# Sensor_LED_2x6_PCB.net
KiCad netlist of a schematic drawn in EAGLE
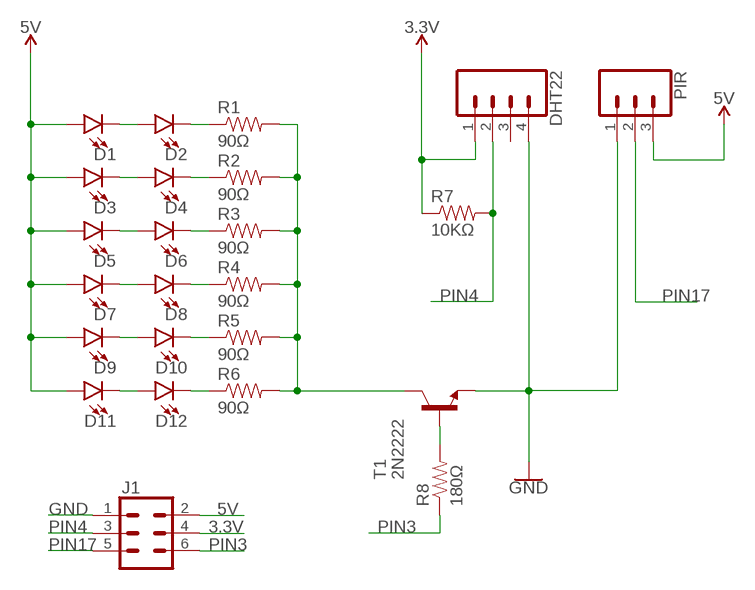
[diagram p0: schematic, sheet 1]

(export (version "E")
  (design (tool "Eeschema 10.0.6"))
  (components
    (comp (ref "D1")
      (value "LED5MM")
      (footprint "eagle-import:LED_5MM")
      (libsource (lib "eagle-import") (part "LED5MM"))
    )
    (comp (ref "D2")
      (value "LED5MM")
      (footprint "eagle-import:LED_5MM")
      (libsource (lib "eagle-import") (part "LED5MM"))
    )
    (comp (ref "D3")
      (value "LED5MM")
      (footprint "eagle-import:LED_5MM")
      (libsource (lib "eagle-import") (part "LED5MM"))
    )
    (comp (ref "D4")
      (value "LED5MM")
      (footprint "eagle-import:LED_5MM")
      (libsource (lib "eagle-import") (part "LED5MM"))
    )
    (comp (ref "D5")
      (value "LED5MM")
      (footprint "eagle-import:LED_5MM")
      (libsource (lib "eagle-import") (part "LED5MM"))
    )
    (comp (ref "D6")
      (value "LED5MM")
      (footprint "eagle-import:LED_5MM")
      (libsource (lib "eagle-import") (part "LED5MM"))
    )
    (comp (ref "D7")
      (value "LED5MM")
      (footprint "eagle-import:LED_5MM")
      (libsource (lib "eagle-import") (part "LED5MM"))
    )
    (comp (ref "D8")
      (value "LED5MM")
      (footprint "eagle-import:LED_5MM")
      (libsource (lib "eagle-import") (part "LED5MM"))
    )
    (comp (ref "D9")
      (value "LED5MM")
      (footprint "eagle-import:LED_5MM")
      (libsource (lib "eagle-import") (part "LED5MM"))
    )
    (comp (ref "D10")
      (value "LED5MM")
      (footprint "eagle-import:LED_5MM")
      (libsource (lib "eagle-import") (part "LED5MM"))
    )
    (comp (ref "D11")
      (value "LED5MM")
      (footprint "eagle-import:LED_5MM")
      (libsource (lib "eagle-import") (part "LED5MM"))
    )
    (comp (ref "D12")
      (value "LED5MM")
      (footprint "eagle-import:LED_5MM")
      (libsource (lib "eagle-import") (part "LED5MM"))
    )
    (comp (ref "DHT22")
      (value "CONN_04LONGPADS")
      (footprint "eagle-import:1X04_LONGPADS")
      (libsource (lib "eagle-import") (part "CONN_04LONGPADS"))
    )
    (comp (ref "J1")
      (value "CONN_03X2SHROUD")
      (footprint "eagle-import:2X3-SHROUDED")
      (libsource (lib "eagle-import") (part "CONN_03X2SHROUD"))
    )
    (comp (ref "PIR")
      (value "CONN_03LONGPADS")
      (footprint "eagle-import:1X03_LONGPADS")
      (libsource (lib "eagle-import") (part "CONN_03LONGPADS"))
    )
    (comp (ref "R1")
      (value "90Ω")
      (footprint "eagle-import:1206")
      (libsource (lib "eagle-import") (part "RESISTOR1206"))
    )
    (comp (ref "R2")
      (value "90Ω")
      (footprint "eagle-import:1206")
      (libsource (lib "eagle-import") (part "RESISTOR1206"))
    )
    (comp (ref "R3")
      (value "90Ω")
      (footprint "eagle-import:1206")
      (libsource (lib "eagle-import") (part "RESISTOR1206"))
    )
    (comp (ref "R4")
      (value "90Ω")
      (footprint "eagle-import:1206")
      (libsource (lib "eagle-import") (part "RESISTOR1206"))
    )
    (comp (ref "R5")
      (value "90Ω")
      (footprint "eagle-import:1206")
      (libsource (lib "eagle-import") (part "RESISTOR1206"))
    )
    (comp (ref "R6")
      (value "90Ω")
      (footprint "eagle-import:1206")
      (libsource (lib "eagle-import") (part "RESISTOR1206"))
    )
    (comp (ref "R7")
      (value "10KΩ")
      (footprint "eagle-import:1206")
      (libsource (lib "eagle-import") (part "RESISTOR1206"))
    )
    (comp (ref "R8")
      (value "180Ω")
      (footprint "eagle-import:1206")
      (libsource (lib "eagle-import") (part "RESISTOR1206"))
    )
    (comp (ref "T1")
      (value "2N2222")
      (footprint "eagle-import:TO92-EBC-OVAL")
      (libsource (lib "eagle-import") (part "2N2222"))
    )
  )
  (nets
    (net (code "1") (name "/PIN3") (class "Default")
      (node (ref "J1") (pin "6") (pinfunction "6_6") (pintype "bidirectional"))
      (node (ref "R8") (pin "1") (pinfunction "1_1") (pintype "passive"))
    )
    (net (code "2") (name "/PIN4") (class "Default")
      (node (ref "DHT22") (pin "2") (pinfunction "2_2") (pintype "passive"))
      (node (ref "J1") (pin "3") (pinfunction "3_3") (pintype "bidirectional"))
      (node (ref "R7") (pin "2") (pinfunction "2_2") (pintype "passive"))
    )
    (net (code "3") (name "/PIN17") (class "Default")
      (node (ref "J1") (pin "5") (pinfunction "5_5") (pintype "bidirectional"))
      (node (ref "PIR") (pin "2") (pinfunction "2_2") (pintype "passive"))
    )
    (net (code "4") (name "3.3V") (class "Default")
      (node (ref "DHT22") (pin "1") (pinfunction "1_1") (pintype "passive"))
      (node (ref "J1") (pin "4") (pinfunction "4_4") (pintype "bidirectional"))
      (node (ref "R7") (pin "1") (pinfunction "1_1") (pintype "passive"))
    )
    (net (code "5") (name "5V") (class "Default")
      (node (ref "D1") (pin "A") (pinfunction "A_A") (pintype "passive"))
      (node (ref "D11") (pin "A") (pinfunction "A_A") (pintype "passive"))
      (node (ref "D3") (pin "A") (pinfunction "A_A") (pintype "passive"))
      (node (ref "D5") (pin "A") (pinfunction "A_A") (pintype "passive"))
      (node (ref "D7") (pin "A") (pinfunction "A_A") (pintype "passive"))
      (node (ref "D9") (pin "A") (pinfunction "A_A") (pintype "passive"))
      (node (ref "J1") (pin "2") (pinfunction "2_2") (pintype "bidirectional"))
      (node (ref "PIR") (pin "3") (pinfunction "3_3") (pintype "passive"))
    )
    (net (code "6") (name "GND") (class "Default")
      (node (ref "DHT22") (pin "4") (pinfunction "4_4") (pintype "passive"))
      (node (ref "J1") (pin "1") (pinfunction "1_1") (pintype "bidirectional"))
      (node (ref "PIR") (pin "1") (pinfunction "1_1") (pintype "passive"))
      (node (ref "T1") (pin "E") (pinfunction "E_E") (pintype "passive"))
    )
    (net (code "7") (name "Net-(D1-C)") (class "Default")
      (node (ref "D1") (pin "K") (pinfunction "C_K") (pintype "passive"))
      (node (ref "D2") (pin "A") (pinfunction "A_A") (pintype "passive"))
    )
    (net (code "8") (name "Net-(D2-C)") (class "Default")
      (node (ref "D2") (pin "K") (pinfunction "C_K") (pintype "passive"))
      (node (ref "R1") (pin "1") (pinfunction "1_1") (pintype "passive"))
    )
    (net (code "9") (name "Net-(D3-C)") (class "Default")
      (node (ref "D3") (pin "K") (pinfunction "C_K") (pintype "passive"))
      (node (ref "D4") (pin "A") (pinfunction "A_A") (pintype "passive"))
    )
    (net (code "10") (name "Net-(D4-C)") (class "Default")
      (node (ref "D4") (pin "K") (pinfunction "C_K") (pintype "passive"))
      (node (ref "R2") (pin "1") (pinfunction "1_1") (pintype "passive"))
    )
    (net (code "11") (name "Net-(D5-C)") (class "Default")
      (node (ref "D5") (pin "K") (pinfunction "C_K") (pintype "passive"))
      (node (ref "D6") (pin "A") (pinfunction "A_A") (pintype "passive"))
    )
    (net (code "12") (name "Net-(D6-C)") (class "Default")
      (node (ref "D6") (pin "K") (pinfunction "C_K") (pintype "passive"))
      (node (ref "R3") (pin "1") (pinfunction "1_1") (pintype "passive"))
    )
    (net (code "13") (name "Net-(D7-C)") (class "Default")
      (node (ref "D7") (pin "K") (pinfunction "C_K") (pintype "passive"))
      (node (ref "D8") (pin "A") (pinfunction "A_A") (pintype "passive"))
    )
    (net (code "14") (name "Net-(D8-C)") (class "Default")
      (node (ref "D8") (pin "K") (pinfunction "C_K") (pintype "passive"))
      (node (ref "R4") (pin "1") (pinfunction "1_1") (pintype "passive"))
    )
    (net (code "15") (name "Net-(D9-C)") (class "Default")
      (node (ref "D10") (pin "A") (pinfunction "A_A") (pintype "passive"))
      (node (ref "D9") (pin "K") (pinfunction "C_K") (pintype "passive"))
    )
    (net (code "16") (name "Net-(D10-C)") (class "Default")
      (node (ref "D10") (pin "K") (pinfunction "C_K") (pintype "passive"))
      (node (ref "R5") (pin "1") (pinfunction "1_1") (pintype "passive"))
    )
    (net (code "17") (name "Net-(D11-C)") (class "Default")
      (node (ref "D11") (pin "K") (pinfunction "C_K") (pintype "passive"))
      (node (ref "D12") (pin "A") (pinfunction "A_A") (pintype "passive"))
    )
    (net (code "18") (name "Net-(D12-C)") (class "Default")
      (node (ref "D12") (pin "K") (pinfunction "C_K") (pintype "passive"))
      (node (ref "R6") (pin "1") (pinfunction "1_1") (pintype "passive"))
    )
    (net (code "19") (name "Net-(R1-Pad2)") (class "Default")
      (node (ref "R1") (pin "2") (pinfunction "2_2") (pintype "passive"))
      (node (ref "R2") (pin "2") (pinfunction "2_2") (pintype "passive"))
      (node (ref "R3") (pin "2") (pinfunction "2_2") (pintype "passive"))
      (node (ref "R4") (pin "2") (pinfunction "2_2") (pintype "passive"))
      (node (ref "R5") (pin "2") (pinfunction "2_2") (pintype "passive"))
      (node (ref "R6") (pin "2") (pinfunction "2_2") (pintype "passive"))
      (node (ref "T1") (pin "C") (pinfunction "C_C") (pintype "passive"))
    )
    (net (code "20") (name "Net-(R8-Pad2)") (class "Default")
      (node (ref "R8") (pin "2") (pinfunction "2_2") (pintype "passive"))
      (node (ref "T1") (pin "B") (pinfunction "B_B") (pintype "passive"))
    )
    (net (code "21") (name "unconnected-(DHT22-Pad3)") (class "Default")
      (node (ref "DHT22") (pin "3") (pinfunction "3_3") (pintype "passive"))
    )
  )
)
